# Power.net
KiCad netlist of a schematic drawn in Altium Designer
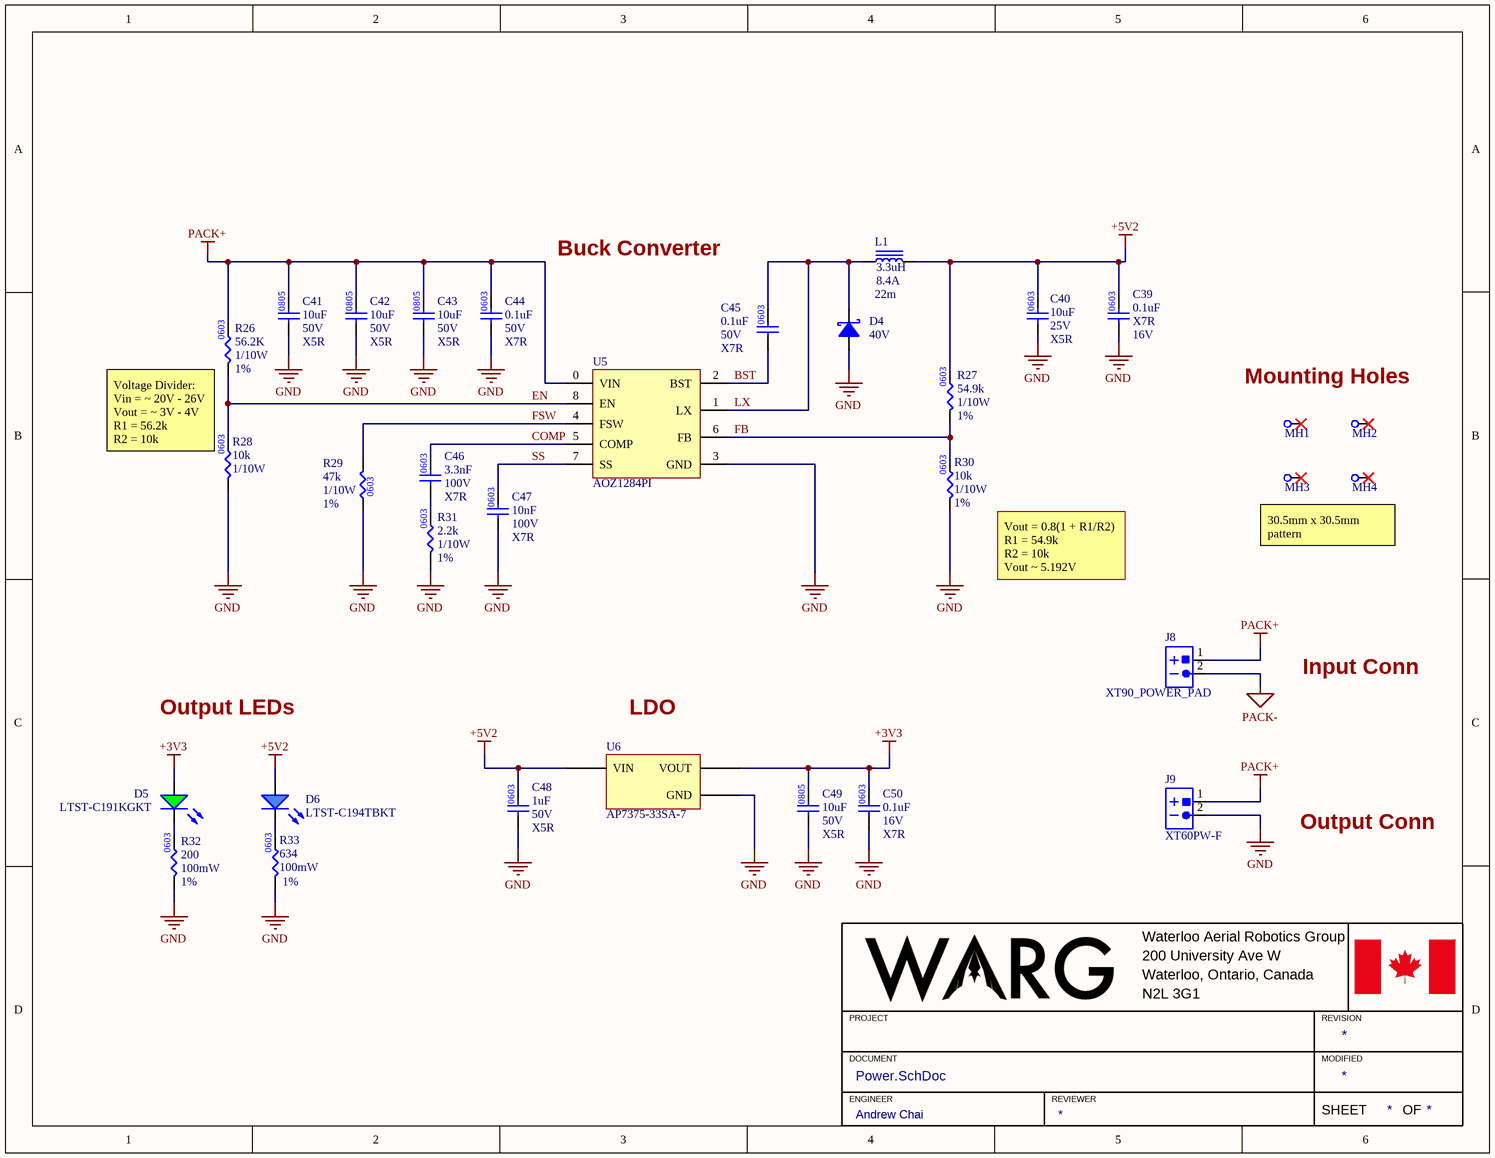
[diagram p0: Power.SchDoc]

(export (version "E")
  (design (tool "Eeschema 10.0.6"))
  (components
    (comp (ref "C39")
      (value "0.1uF")
      (footprint ".CAP_0603-Footprint-1")
      (description "CAP CER 0.1uF 16V X7R 0603")
      (fields
        (field (name "TEMPERATURE COEFFICIENT") "X7R")
        (field (name "VOLTAGE") "16V")
        (field (name "Comment") "GCM188R71C104KA37D")
      )
      (libsource (lib "WARG") (part ".CAP_0603-Symbol-1"))
    )
    (comp (ref "C40")
      (value "10uF")
      (footprint ".CAP_0603-Footprint-1")
      (description "CAP CER 10UF 25V X5R 0603")
      (fields
        (field (name "VOLTAGE RATING") "25V")
        (field (name "TEMPERATURE COEFFICIENT") "X5R")
        (field (name "Comment") "GRM188R61E106KA73J")
      )
      (libsource (lib "WARG") (part ".CAP_0603-Symbol-1"))
    )
    (comp (ref "C41")
      (value "10uF")
      (footprint ".CAP_0805-Footprint-1")
      (description "CAP CER 10uF 50V X5R 0805")
      (fields
        (field (name "VOLTAGE") "50V")
        (field (name "VOLTAGE RATING") "50V")
        (field (name "DIELECTRIC") "X5R")
        (field (name "Comment") "GRM21BR61H106KE43L")
      )
      (libsource (lib "WARG") (part ".CAP_0805-Symbol-1"))
    )
    (comp (ref "C42")
      (value "10uF")
      (footprint ".CAP_0805-Footprint-1")
      (description "CAP CER 10uF 50V X5R 0805")
      (fields
        (field (name "VOLTAGE") "50V")
        (field (name "VOLTAGE RATING") "50V")
        (field (name "DIELECTRIC") "X5R")
        (field (name "Comment") "GRM21BR61H106KE43L")
      )
      (libsource (lib "WARG") (part ".CAP_0805-Symbol-1"))
    )
    (comp (ref "C43")
      (value "10uF")
      (footprint ".CAP_0805-Footprint-1")
      (description "CAP CER 10uF 50V X5R 0805")
      (fields
        (field (name "VOLTAGE") "50V")
        (field (name "VOLTAGE RATING") "50V")
        (field (name "DIELECTRIC") "X5R")
        (field (name "Comment") "GRM21BR61H106KE43L")
      )
      (libsource (lib "WARG") (part ".CAP_0805-Symbol-1"))
    )
    (comp (ref "C44")
      (value "GCM188R71H104KA57D")
      (footprint "CAP0603")
      (description "CAP CER 0.1uF 50V X7R 0603")
      (fields
        (field (name "VOLTAGE") "50V")
        (field (name "DIELECTRIC") "X7R")
        (field (name "CAPACITANCE") "0.1uF")
        (field (name "TOLERANCE") "10%")
      )
      (libsource (lib "WARG") (part "CAP-NP-2"))
    )
    (comp (ref "C45")
      (value "GCM188R71H104KA57D")
      (footprint "CAP0603")
      (description "CAP CER 0.1uF 50V X7R 0603")
      (fields
        (field (name "VOLTAGE") "50V")
        (field (name "DIELECTRIC") "X7R")
        (field (name "CAPACITANCE") "0.1uF")
        (field (name "TOLERANCE") "10%")
      )
      (libsource (lib "WARG") (part "CAP-NP-2"))
    )
    (comp (ref "C46")
      (value "3.3nF")
      (footprint ".CAP_0603-Footprint-1")
      (fields
        (field (name "TEMPERATURE CHARACTERISTICS CODE") "X7R")
        (field (name "RATED DC VOLTAGE (URDC)") "100V")
        (field (name "Comment") "GCM188R72A332KA37D")
      )
      (libsource (lib "WARG") (part ".CAP_0603-Symbol-1"))
    )
    (comp (ref "C47")
      (value "10nF")
      (footprint "CAP0603")
      (description "CAP CER 10000PF 100V X7R 0603")
      (fields
        (field (name "RATED DC VOLTAGE (URDC)") "100V")
        (field (name "TOLERANCE") "10%")
        (field (name "TEMPERATURE CHARACTERISTICS CODE") "X7R")
        (field (name "Comment") "GCM188R72A103KA37D")
      )
      (libsource (lib "WARG") (part "CAP"))
    )
    (comp (ref "C48")
      (value "1uF")
      (footprint ".CAP_0603-Footprint-1")
      (description "CAP CER 1UF 50V X5R 0603")
      (fields
        (field (name "VOLTAGE RATING") "50V")
        (field (name "TEMPERATURE CHARACTERISTICS CODE") "X5R")
        (field (name "TOLERANCE") "10%")
        (field (name "Comment") "GRT188R61H105KE13D")
      )
      (libsource (lib "WARG") (part "CAP"))
    )
    (comp (ref "C49")
      (value "10uF")
      (footprint ".CAP_0805-Footprint-1")
      (description "CAP CER 10uF 50V X5R 0805")
      (fields
        (field (name "VOLTAGE") "50V")
        (field (name "VOLTAGE RATING") "50V")
        (field (name "DIELECTRIC") "X5R")
        (field (name "Comment") "GRM21BR61H106KE43L")
      )
      (libsource (lib "WARG") (part ".CAP_0805-Symbol-1"))
    )
    (comp (ref "C50")
      (value "0.1uF")
      (footprint ".CAP_0603-Footprint-1")
      (description "CAP CER 0.1uF 16V X7R 0603")
      (fields
        (field (name "TEMPERATURE COEFFICIENT") "X7R")
        (field (name "VOLTAGE") "16V")
        (field (name "Comment") "GCM188R71C104KA37D")
      )
      (libsource (lib "WARG") (part ".CAP_0603-Symbol-1"))
    )
    (comp (ref "D4")
      (value "SK54A-LTP")
      (footprint "DIOM4426X24N")
      (description "Diode Schottky 40V 5A 2-Pin SMA T/R")
      (fields (field (name "MAX REVERSE VOLTAGE (DC)") "40V"))
      (libsource (lib "WARG") (part ".SCHOTTKY-Symbol-1"))
    )
    (comp (ref "D5")
      (value "LTST-C191KGKT")
      (footprint ".LED_0603-Footprint-1")
      (description "LED GREEN 2V 0603")
      (libsource (lib "WARG") (part "LTST-C191KGKT-Symbol-1"))
    )
    (comp (ref "D6")
      (value "LTST-C194TBKT")
      (footprint "LTST-C194TBKT-Footprint-1")
      (description "LED BLUE CLEAR 0603 SMD")
      (fields (field (name "VOLTAGE") "29V"))
      (libsource (lib "WARG") (part "LTST-C194TBKT"))
    )
    (comp (ref "J8")
      (value "XT90_POWER_PAD")
      (footprint "XT90_POWER_PAD-Footprint-1")
      (description "XT90_POWER_PAD, 4.5mm Square Pad, 6.5mm Pitch")
      (libsource (lib "WARG") (part "XT90_POWER_PAD"))
    )
    (comp (ref "J9")
      (value "XT60PW-F")
      (footprint "XT60PW-F-Footprint-1")
      (description "Board Mount XT60PW-F 2 Pin Female Connector")
      (fields (field (name "MANUFACTURER") "TME"))
      (libsource (lib "WARG") (part "XT60PW-M-Symbol-1"))
    )
    (comp (ref "L1")
      (value "0630CDMCCDS-3R3MC")
      (footprint "0630CDMCCDS-3R3MC-Footprint-1")
      (description "General Purpose Inductor, 3.3uH, 20%, 1 Element, SMD")
      (fields
        (field (name "DC RESISTANCE") "22m")
        (field (name "TOLERANCE") "+/- 20%")
        (field (name "CURRENT") "8.4A")
        (field (name "INDUCTANCE") "3.3uH")
      )
      (libsource (lib "WARG") (part ".IND-Symbol-1"))
    )
    (comp (ref "MH1")
      (value "M2HOLE-STANDARD")
      (footprint "M2HOLE-STANDARD-Footprint-1")
      (description "RFC in progress (Dimensions currently unapproved)")
      (libsource (lib "WARG") (part "M2HOLE-STANDARD-Symbol-1"))
    )
    (comp (ref "MH2")
      (value "M2HOLE-STANDARD")
      (footprint "M2HOLE-STANDARD-Footprint-1")
      (description "RFC in progress (Dimensions currently unapproved)")
      (libsource (lib "WARG") (part "M2HOLE-STANDARD-Symbol-1"))
    )
    (comp (ref "MH3")
      (value "M2HOLE-STANDARD")
      (footprint "M2HOLE-STANDARD-Footprint-1")
      (description "RFC in progress (Dimensions currently unapproved)")
      (libsource (lib "WARG") (part "M2HOLE-STANDARD-Symbol-1"))
    )
    (comp (ref "MH4")
      (value "M2HOLE-STANDARD")
      (footprint "M2HOLE-STANDARD-Footprint-1")
      (description "RFC in progress (Dimensions currently unapproved)")
      (libsource (lib "WARG") (part "M2HOLE-STANDARD-Symbol-1"))
    )
    (comp (ref "R26")
      (value "56.2K")
      (footprint ".RES_0603-Footprint-1")
      (description "RES 56.2K OHM 1% 1/10W 0603")
      (fields
        (field (name "POWER") "1/10W")
        (field (name "TOLERANCE") "1%")
        (field (name "Comment") "RC0603FR-0756K2L")
      )
      (libsource (lib "WARG") (part ".RES_0603-Symbol-1"))
    )
    (comp (ref "R27")
      (value "RC0603FR-0754K9L")
      (footprint ".RES_0603-Footprint-1")
      (description "RES 54.9k OHM 1% 1/10@ 0603")
      (fields
        (field (name "POWER RATING") "1/10W")
        (field (name "RESISTANCE") "54.9k")
        (field (name "TOLERANCE") "1%")
      )
      (libsource (lib "WARG") (part ".RES_0603-Symbol-1"))
    )
    (comp (ref "R28")
      (value "10k")
      (footprint ".RES_0603-Footprint-1")
      (description "RES 10K OHM 1% 1/10W 0603")
      (fields
        (field (name "POWER") "1/10W")
        (field (name "TOLERANCE") "1%")
        (field (name "Comment") "RC0603FR-0710KL")
      )
      (libsource (lib "WARG") (part ".RES_0603-Symbol-1"))
    )
    (comp (ref "R29")
      (value "47k")
      (footprint "RC0603FR-0756K2L-Footprint-1")
      (description "RES 47K OHM 1% 1/10W 0603")
      (fields
        (field (name "POWER") "1/10W")
        (field (name "TOLERANCE") "1%")
        (field (name "Comment") "RC0603FR-0747KL")
      )
      (libsource (lib "WARG") (part "RC0603FR-0740K2L-Symbol-1"))
    )
    (comp (ref "R30")
      (value "10k")
      (footprint ".RES_0603-Footprint-1")
      (description "RES 10K OHM 1% 1/10W 0603")
      (fields
        (field (name "POWER") "1/10W")
        (field (name "TOLERANCE") "1%")
        (field (name "Comment") "RC0603FR-0710KL")
      )
      (libsource (lib "WARG") (part ".RES_0603-Symbol-1"))
    )
    (comp (ref "R31")
      (value "2.2k")
      (footprint ".RES_0603-Footprint-1")
      (description "RES 2.2K OHM 0603 1/10W")
      (fields
        (field (name "RESISTANCE TOLERANCE") "1%")
        (field (name "MAX POWER DISSIPATION") "1/10W")
        (field (name "Comment") "RC0603FR-072K2L")
      )
      (libsource (lib "WARG") (part ".RES_0603-Symbol-1"))
    )
    (comp (ref "R32")
      (value "RC0603FR-07200RL")
      (footprint ".RES_0603-Footprint-1")
      (description "RES 200 OHM 1% 1/10W 0603")
      (fields
        (field (name "TOLERANCE") "1%")
        (field (name "POWER RATING") "100mW")
        (field (name "RESISTANCE") "200")
      )
      (libsource (lib "WARG") (part ".RES_0603-Symbol-1"))
    )
    (comp (ref "R33")
      (value "634")
      (footprint ".RES_0603-Footprint-1")
      (description "RES 634 OHM 1% 1/10W 0603")
      (fields
        (field (name "TOLERANCE") "1%")
        (field (name "POWER") "100mW")
        (field (name "Comment") "RC0603FR-07634RL")
      )
      (libsource (lib "WARG") (part "RES-2"))
    )
    (comp (ref "U5")
      (value "AOZ1284PI")
      (footprint "AOZ1284PI-Footprint-1")
      (description "IC REG BUCK ADJUSTABLE 4A 8SO")
      (fields (field (name "MANUFACTURER PART NUMBER 1") "AOZ1284PI"))
      (libsource (lib "WARG") (part "AOZ1284PI"))
    )
    (comp (ref "U6")
      (value "AP7375-33SA-7")
      (footprint "AP7375-33SA-7-Footprint-1")
      (description "IC REG LIN 3.3V 300MA SOT23-3")
      (libsource (lib "WARG") (part "AP7375-33SA-7"))
    )
  )
  (nets
    (net (code "1") (name "+3V3") (class "Default")
      (node (ref "C49") (pin "2") (pinfunction "2_2") (pintype "passive"))
      (node (ref "C50") (pin "2") (pinfunction "2_2") (pintype "passive"))
      (node (ref "D5") (pin "1") (pinfunction "A_1") (pintype "passive"))
      (node (ref "U6") (pin "2") (pinfunction "VOUT_2") (pintype "passive"))
    )
    (net (code "2") (name "+5V2") (class "Default")
      (node (ref "C39") (pin "2") (pinfunction "2_2") (pintype "passive"))
      (node (ref "C40") (pin "2") (pinfunction "2_2") (pintype "passive"))
      (node (ref "C48") (pin "2") (pinfunction "2_2") (pintype "passive"))
      (node (ref "D6") (pin "1") (pinfunction "A_1") (pintype "passive"))
      (node (ref "L1") (pin "2") (pinfunction "2_2") (pintype "passive"))
      (node (ref "R27") (pin "2") (pinfunction "2_2") (pintype "passive"))
      (node (ref "U6") (pin "1") (pinfunction "VIN_1") (pintype "passive"))
    )
    (net (code "3") (name "/BST") (class "Default")
      (node (ref "C45") (pin "1") (pinfunction "1_1") (pintype "passive"))
      (node (ref "U5") (pin "2") (pinfunction "BST_2") (pintype "passive"))
    )
    (net (code "4") (name "/COMP") (class "Default")
      (node (ref "C46") (pin "2") (pinfunction "2_2") (pintype "passive"))
      (node (ref "U5") (pin "5") (pinfunction "COMP_5") (pintype "passive"))
    )
    (net (code "5") (name "/EN") (class "Default")
      (node (ref "R26") (pin "1") (pinfunction "1_1") (pintype "passive"))
      (node (ref "R28") (pin "2") (pinfunction "2_2") (pintype "passive"))
      (node (ref "U5") (pin "8") (pinfunction "EN_8") (pintype "passive"))
    )
    (net (code "6") (name "/FB") (class "Default")
      (node (ref "R27") (pin "1") (pinfunction "1_1") (pintype "passive"))
      (node (ref "R30") (pin "2") (pinfunction "2_2") (pintype "passive"))
      (node (ref "U5") (pin "6") (pinfunction "FB_6") (pintype "passive"))
    )
    (net (code "7") (name "/FSW") (class "Default")
      (node (ref "R29") (pin "2") (pinfunction "2_2") (pintype "passive"))
      (node (ref "U5") (pin "4") (pinfunction "FSW_4") (pintype "passive"))
    )
    (net (code "8") (name "/LX") (class "Default")
      (node (ref "C45") (pin "2") (pinfunction "2_2") (pintype "passive"))
      (node (ref "D4") (pin "2") (pinfunction "Cathode_2") (pintype "passive"))
      (node (ref "L1") (pin "1") (pinfunction "1_1") (pintype "passive"))
      (node (ref "U5") (pin "1") (pinfunction "LX_1") (pintype "passive"))
    )
    (net (code "9") (name "/SS") (class "Default")
      (node (ref "C47") (pin "2") (pinfunction "2_2") (pintype "passive"))
      (node (ref "U5") (pin "7") (pinfunction "SS_7") (pintype "passive"))
    )
    (net (code "10") (name "GND") (class "Default")
      (node (ref "C39") (pin "1") (pinfunction "1_1") (pintype "passive"))
      (node (ref "C40") (pin "1") (pinfunction "1_1") (pintype "passive"))
      (node (ref "C41") (pin "1") (pinfunction "1_1") (pintype "passive"))
      (node (ref "C42") (pin "1") (pinfunction "1_1") (pintype "passive"))
      (node (ref "C43") (pin "1") (pinfunction "1_1") (pintype "passive"))
      (node (ref "C44") (pin "1") (pinfunction "1_1") (pintype "passive"))
      (node (ref "C47") (pin "1") (pinfunction "1_1") (pintype "passive"))
      (node (ref "C48") (pin "1") (pinfunction "1_1") (pintype "passive"))
      (node (ref "C49") (pin "1") (pinfunction "1_1") (pintype "passive"))
      (node (ref "C50") (pin "1") (pinfunction "1_1") (pintype "passive"))
      (node (ref "D4") (pin "1") (pinfunction "Anode_1") (pintype "passive"))
      (node (ref "J9") (pin "2") (pinfunction "2_2") (pintype "passive"))
      (node (ref "R28") (pin "1") (pinfunction "1_1") (pintype "passive"))
      (node (ref "R29") (pin "1") (pinfunction "1_1") (pintype "passive"))
      (node (ref "R30") (pin "1") (pinfunction "1_1") (pintype "passive"))
      (node (ref "R31") (pin "1") (pinfunction "1_1") (pintype "passive"))
      (node (ref "R32") (pin "1") (pinfunction "1_1") (pintype "passive"))
      (node (ref "R33") (pin "1") (pinfunction "1_1") (pintype "passive"))
      (node (ref "U5") (pin "3") (pinfunction "GND_3") (pintype "passive"))
      (node (ref "U6") (pin "3") (pinfunction "GND_3") (pintype "passive"))
    )
    (net (code "11") (name "Net-(C46-Pad1)") (class "Default")
      (node (ref "C46") (pin "1") (pinfunction "1_1") (pintype "passive"))
      (node (ref "R31") (pin "2") (pinfunction "2_2") (pintype "passive"))
    )
    (net (code "12") (name "Net-(D5-K)") (class "Default")
      (node (ref "D5") (pin "2") (pinfunction "K_2") (pintype "passive"))
      (node (ref "R32") (pin "2") (pinfunction "2_2") (pintype "passive"))
    )
    (net (code "13") (name "Net-(D6-K)") (class "Default")
      (node (ref "D6") (pin "2") (pinfunction "K_2") (pintype "passive"))
      (node (ref "R33") (pin "2") (pinfunction "2_2") (pintype "passive"))
    )
    (net (code "14") (name "PACK+") (class "Default")
      (node (ref "C41") (pin "2") (pinfunction "2_2") (pintype "passive"))
      (node (ref "C42") (pin "2") (pinfunction "2_2") (pintype "passive"))
      (node (ref "C43") (pin "2") (pinfunction "2_2") (pintype "passive"))
      (node (ref "C44") (pin "2") (pinfunction "2_2") (pintype "passive"))
      (node (ref "J8") (pin "1") (pinfunction "1_1") (pintype "passive"))
      (node (ref "J9") (pin "1") (pinfunction "1_1") (pintype "passive"))
      (node (ref "R26") (pin "2") (pinfunction "2_2") (pintype "passive"))
      (node (ref "U5") (pin "0") (pinfunction "VIN_0") (pintype "passive"))
    )
    (net (code "15") (name "PACK-") (class "Default")
      (node (ref "J8") (pin "2") (pinfunction "2_2") (pintype "passive"))
    )
    (net (code "16") (name "unconnected-(MH1-Pad1)") (class "Default")
      (node (ref "MH1") (pin "1") (pinfunction "1_1") (pintype "passive+no_connect"))
    )
    (net (code "17") (name "unconnected-(MH2-Pad1)") (class "Default")
      (node (ref "MH2") (pin "1") (pinfunction "1_1") (pintype "passive+no_connect"))
    )
    (net (code "18") (name "unconnected-(MH3-Pad1)") (class "Default")
      (node (ref "MH3") (pin "1") (pinfunction "1_1") (pintype "passive+no_connect"))
    )
    (net (code "19") (name "unconnected-(MH4-Pad1)") (class "Default")
      (node (ref "MH4") (pin "1") (pinfunction "1_1") (pintype "passive+no_connect"))
    )
  )
)
